# TESTESP1SH.net
KiCad netlist of a schematic drawn in EAGLE
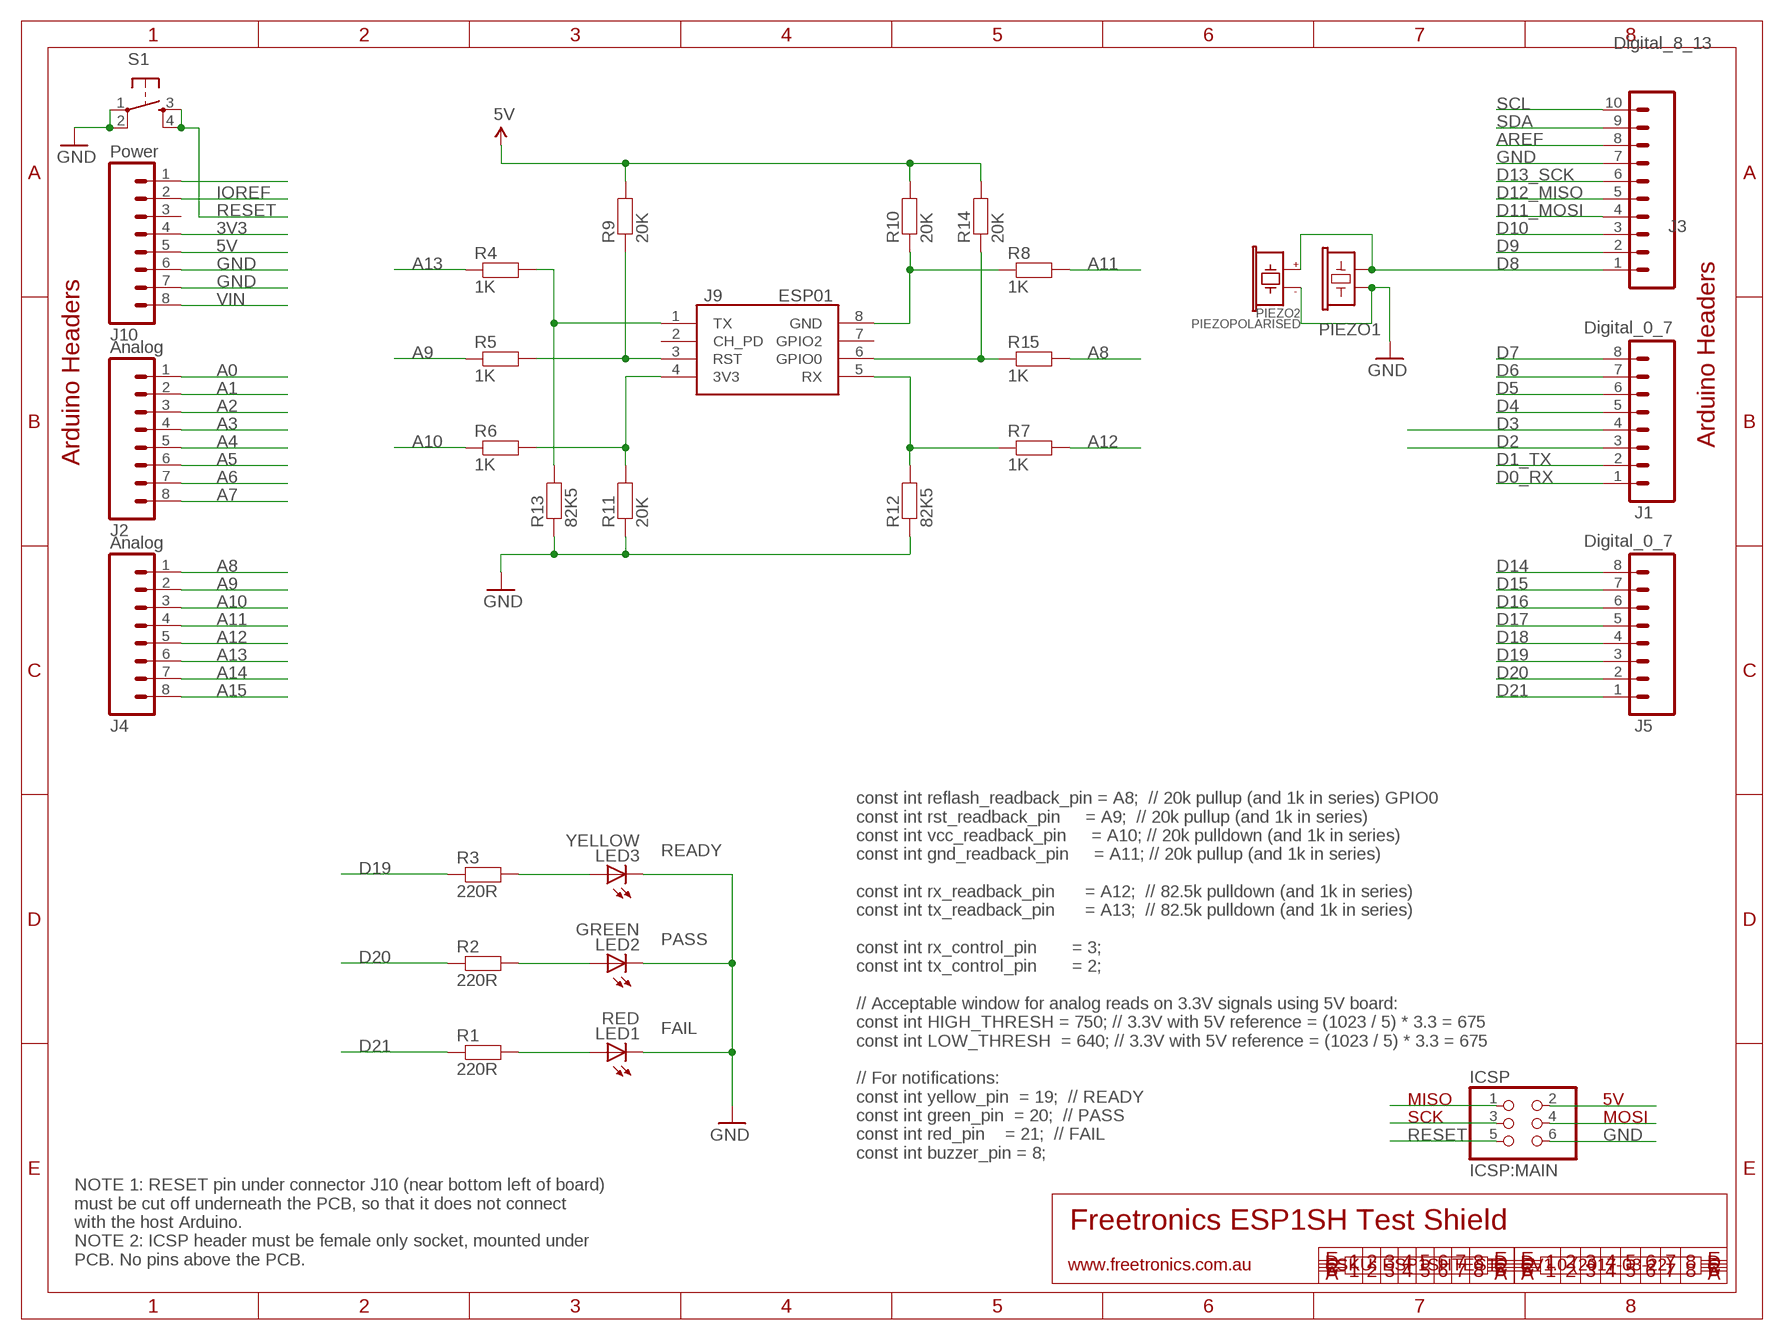
[diagram p0: schematic, sheet 1]

(export (version "E")
  (design (tool "Eeschema 10.0.6"))
  (components
    (comp (ref "ICSP")
      (value "ICSP:MAIN")
      (footprint "eagle-import:2X03")
      (libsource (lib "eagle-import") (part "PINHD-2X3"))
    )
    (comp (ref "J1")
      (value "Digital_0_7")
      (footprint "eagle-import:1X08")
      (libsource (lib "eagle-import") (part "M08"))
    )
    (comp (ref "J2")
      (value "Analog")
      (footprint "eagle-import:1X08")
      (libsource (lib "eagle-import") (part "freetronics-master-v1_M08"))
    )
    (comp (ref "J3")
      (value "Digital_8_13")
      (footprint "eagle-import:1X10")
      (libsource (lib "eagle-import") (part "M100.1"))
    )
    (comp (ref "J4")
      (value "Analog")
      (footprint "eagle-import:1X08")
      (libsource (lib "eagle-import") (part "freetronics-master-v1_M08"))
    )
    (comp (ref "J5")
      (value "Digital_0_7")
      (footprint "eagle-import:1X08")
      (libsource (lib "eagle-import") (part "M08"))
    )
    (comp (ref "J9")
      (value "ESP01")
      (footprint "eagle-import:ESP01")
      (libsource (lib "eagle-import") (part "ESP01"))
    )
    (comp (ref "J10")
      (value "Power")
      (footprint "eagle-import:1X08")
      (libsource (lib "eagle-import") (part "freetronics-master-v1_M08"))
    )
    (comp (ref "LED1")
      (value "RED")
      (footprint "eagle-import:LED-0603")
      (libsource (lib "eagle-import") (part "LED0603"))
    )
    (comp (ref "LED2")
      (value "GREEN")
      (footprint "eagle-import:LED-0603")
      (libsource (lib "eagle-import") (part "LED0603"))
    )
    (comp (ref "LED3")
      (value "YELLOW")
      (footprint "eagle-import:LED-0603")
      (libsource (lib "eagle-import") (part "LED0603"))
    )
    (comp (ref "PIEZO1")
      (value "BUZZERSMD12X12")
      (footprint "eagle-import:BUZZER-12X12-SMT")
      (libsource (lib "eagle-import") (part "BUZZERSMD12X12"))
    )
    (comp (ref "PIEZO2")
      (value "PIEZOPOLARISED")
      (footprint "eagle-import:PIEZO12MMWIDEPOLARISED")
      (libsource (lib "eagle-import") (part "PIEZOPOLARISED"))
    )
    (comp (ref "R1")
      (value "220R")
      (footprint "eagle-import:0603")
      (libsource (lib "eagle-import") (part "RESISTOR0603"))
    )
    (comp (ref "R2")
      (value "220R")
      (footprint "eagle-import:0603")
      (libsource (lib "eagle-import") (part "RESISTOR0603"))
    )
    (comp (ref "R3")
      (value "220R")
      (footprint "eagle-import:0603")
      (libsource (lib "eagle-import") (part "RESISTOR0603"))
    )
    (comp (ref "R4")
      (value "1K")
      (footprint "eagle-import:0603")
      (libsource (lib "eagle-import") (part "RESISTOR0603"))
    )
    (comp (ref "R5")
      (value "1K")
      (footprint "eagle-import:0603")
      (libsource (lib "eagle-import") (part "RESISTOR0603"))
    )
    (comp (ref "R6")
      (value "1K")
      (footprint "eagle-import:0603")
      (libsource (lib "eagle-import") (part "RESISTOR0603"))
    )
    (comp (ref "R7")
      (value "1K")
      (footprint "eagle-import:0603")
      (libsource (lib "eagle-import") (part "RESISTOR0603"))
    )
    (comp (ref "R8")
      (value "1K")
      (footprint "eagle-import:0603")
      (libsource (lib "eagle-import") (part "RESISTOR0603"))
    )
    (comp (ref "R9")
      (value "20K")
      (footprint "eagle-import:0603")
      (libsource (lib "eagle-import") (part "RESISTOR0603"))
    )
    (comp (ref "R10")
      (value "20K")
      (footprint "eagle-import:0603")
      (libsource (lib "eagle-import") (part "RESISTOR0603"))
    )
    (comp (ref "R11")
      (value "20K")
      (footprint "eagle-import:0603")
      (libsource (lib "eagle-import") (part "RESISTOR0603"))
    )
    (comp (ref "R12")
      (value "82K5")
      (footprint "eagle-import:0603")
      (libsource (lib "eagle-import") (part "RESISTOR0603"))
    )
    (comp (ref "R13")
      (value "82K5")
      (footprint "eagle-import:0603")
      (libsource (lib "eagle-import") (part "RESISTOR0603"))
    )
    (comp (ref "R14")
      (value "20K")
      (footprint "eagle-import:0603")
      (libsource (lib "eagle-import") (part "RESISTOR0603"))
    )
    (comp (ref "R15")
      (value "1K")
      (footprint "eagle-import:0603")
      (libsource (lib "eagle-import") (part "RESISTOR0603"))
    )
    (comp (ref "S1")
      (value "TAC_SWITCHPTH")
      (footprint "eagle-import:TACTILE-PTH")
      (libsource (lib "eagle-import") (part "TAC_SWITCHPTH"))
    )
  )
  (nets
    (net (code "1") (name "/3V3") (class "Default")
      (node (ref "J10") (pin "4") (pinfunction "4_4") (pintype "passive"))
    )
    (net (code "2") (name "/A0") (class "Default")
      (node (ref "J2") (pin "1") (pinfunction "1_1") (pintype "passive"))
    )
    (net (code "3") (name "/A1") (class "Default")
      (node (ref "J2") (pin "2") (pinfunction "2_2") (pintype "passive"))
    )
    (net (code "4") (name "/A2") (class "Default")
      (node (ref "J2") (pin "3") (pinfunction "3_3") (pintype "passive"))
    )
    (net (code "5") (name "/A3") (class "Default")
      (node (ref "J2") (pin "4") (pinfunction "4_4") (pintype "passive"))
    )
    (net (code "6") (name "/A4") (class "Default")
      (node (ref "J2") (pin "5") (pinfunction "5_5") (pintype "passive"))
    )
    (net (code "7") (name "/A5") (class "Default")
      (node (ref "J2") (pin "6") (pinfunction "6_6") (pintype "passive"))
    )
    (net (code "8") (name "/A6") (class "Default")
      (node (ref "J2") (pin "7") (pinfunction "7_7") (pintype "passive"))
    )
    (net (code "9") (name "/A7") (class "Default")
      (node (ref "J2") (pin "8") (pinfunction "8_8") (pintype "passive"))
    )
    (net (code "10") (name "/A8") (class "Default")
      (node (ref "J4") (pin "1") (pinfunction "1_1") (pintype "passive"))
      (node (ref "R15") (pin "2") (pinfunction "2_2") (pintype "passive"))
    )
    (net (code "11") (name "/A9") (class "Default")
      (node (ref "J4") (pin "2") (pinfunction "2_2") (pintype "passive"))
      (node (ref "R5") (pin "1") (pinfunction "1_1") (pintype "passive"))
    )
    (net (code "12") (name "/A10") (class "Default")
      (node (ref "J4") (pin "3") (pinfunction "3_3") (pintype "passive"))
      (node (ref "R6") (pin "1") (pinfunction "1_1") (pintype "passive"))
    )
    (net (code "13") (name "/A11") (class "Default")
      (node (ref "J4") (pin "4") (pinfunction "4_4") (pintype "passive"))
      (node (ref "R8") (pin "2") (pinfunction "2_2") (pintype "passive"))
    )
    (net (code "14") (name "/A12") (class "Default")
      (node (ref "J4") (pin "5") (pinfunction "5_5") (pintype "passive"))
      (node (ref "R7") (pin "2") (pinfunction "2_2") (pintype "passive"))
    )
    (net (code "15") (name "/A13") (class "Default")
      (node (ref "J4") (pin "6") (pinfunction "6_6") (pintype "passive"))
      (node (ref "R4") (pin "1") (pinfunction "1_1") (pintype "passive"))
    )
    (net (code "16") (name "/A14") (class "Default")
      (node (ref "J4") (pin "7") (pinfunction "7_7") (pintype "passive"))
    )
    (net (code "17") (name "/A15") (class "Default")
      (node (ref "J4") (pin "8") (pinfunction "8_8") (pintype "passive"))
    )
    (net (code "18") (name "/AREF") (class "Default")
      (node (ref "J3") (pin "8") (pinfunction "8_8") (pintype "passive"))
    )
    (net (code "19") (name "/D0_RX") (class "Default")
      (node (ref "J1") (pin "1") (pinfunction "1_1") (pintype "passive"))
    )
    (net (code "20") (name "/D1_TX") (class "Default")
      (node (ref "J1") (pin "2") (pinfunction "2_2") (pintype "passive"))
    )
    (net (code "21") (name "/D2") (class "Default")
      (node (ref "J1") (pin "3") (pinfunction "3_3") (pintype "passive"))
    )
    (net (code "22") (name "/D3") (class "Default")
      (node (ref "J1") (pin "4") (pinfunction "4_4") (pintype "passive"))
    )
    (net (code "23") (name "/D4") (class "Default")
      (node (ref "J1") (pin "5") (pinfunction "5_5") (pintype "passive"))
    )
    (net (code "24") (name "/D5") (class "Default")
      (node (ref "J1") (pin "6") (pinfunction "6_6") (pintype "passive"))
    )
    (net (code "25") (name "/D6") (class "Default")
      (node (ref "J1") (pin "7") (pinfunction "7_7") (pintype "passive"))
    )
    (net (code "26") (name "/D7") (class "Default")
      (node (ref "J1") (pin "8") (pinfunction "8_8") (pintype "passive"))
    )
    (net (code "27") (name "/D8") (class "Default")
      (node (ref "J3") (pin "1") (pinfunction "1_1") (pintype "passive"))
      (node (ref "PIEZO1") (pin "1") (pinfunction "1_1") (pintype "passive"))
      (node (ref "PIEZO2") (pin "1") (pinfunction "+_1") (pintype "bidirectional"))
    )
    (net (code "28") (name "/D9") (class "Default")
      (node (ref "J3") (pin "2") (pinfunction "2_2") (pintype "passive"))
    )
    (net (code "29") (name "/D10") (class "Default")
      (node (ref "J3") (pin "3") (pinfunction "3_3") (pintype "passive"))
    )
    (net (code "30") (name "/D11_MOSI") (class "Default")
      (node (ref "J3") (pin "4") (pinfunction "4_4") (pintype "passive"))
    )
    (net (code "31") (name "/D12_MISO") (class "Default")
      (node (ref "J3") (pin "5") (pinfunction "5_5") (pintype "passive"))
    )
    (net (code "32") (name "/D13_SCK") (class "Default")
      (node (ref "J3") (pin "6") (pinfunction "6_6") (pintype "passive"))
    )
    (net (code "33") (name "/D14") (class "Default")
      (node (ref "J5") (pin "8") (pinfunction "8_8") (pintype "passive"))
    )
    (net (code "34") (name "/D15") (class "Default")
      (node (ref "J5") (pin "7") (pinfunction "7_7") (pintype "passive"))
    )
    (net (code "35") (name "/D16") (class "Default")
      (node (ref "J5") (pin "6") (pinfunction "6_6") (pintype "passive"))
    )
    (net (code "36") (name "/D17") (class "Default")
      (node (ref "J5") (pin "5") (pinfunction "5_5") (pintype "passive"))
    )
    (net (code "37") (name "/D18") (class "Default")
      (node (ref "J5") (pin "4") (pinfunction "4_4") (pintype "passive"))
    )
    (net (code "38") (name "/D19") (class "Default")
      (node (ref "J5") (pin "3") (pinfunction "3_3") (pintype "passive"))
      (node (ref "R3") (pin "1") (pinfunction "1_1") (pintype "passive"))
    )
    (net (code "39") (name "/D20") (class "Default")
      (node (ref "J5") (pin "2") (pinfunction "2_2") (pintype "passive"))
      (node (ref "R2") (pin "1") (pinfunction "1_1") (pintype "passive"))
    )
    (net (code "40") (name "/D21") (class "Default")
      (node (ref "J5") (pin "1") (pinfunction "1_1") (pintype "passive"))
      (node (ref "R1") (pin "1") (pinfunction "1_1") (pintype "passive"))
    )
    (net (code "41") (name "/IOREF") (class "Default")
      (node (ref "J10") (pin "2") (pinfunction "2_2") (pintype "passive"))
    )
    (net (code "42") (name "/RESET") (class "Default")
      (node (ref "ICSP") (pin "5") (pinfunction "5_5") (pintype "passive"))
      (node (ref "S1") (pin "3") (pinfunction "3_3") (pintype "passive"))
      (node (ref "S1") (pin "4") (pinfunction "4_4") (pintype "passive"))
    )
    (net (code "43") (name "/SCL") (class "Default")
      (node (ref "J3") (pin "10") (pinfunction "10_10") (pintype "passive"))
    )
    (net (code "44") (name "/SDA") (class "Default")
      (node (ref "J3") (pin "9") (pinfunction "9_9") (pintype "passive"))
    )
    (net (code "45") (name "/VIN") (class "Default")
      (node (ref "J10") (pin "8") (pinfunction "8_8") (pintype "passive"))
    )
    (net (code "46") (name "5V") (class "Default")
      (node (ref "J10") (pin "5") (pinfunction "5_5") (pintype "passive"))
      (node (ref "R10") (pin "2") (pinfunction "2_2") (pintype "passive"))
      (node (ref "R14") (pin "2") (pinfunction "2_2") (pintype "passive"))
      (node (ref "R9") (pin "2") (pinfunction "2_2") (pintype "passive"))
    )
    (net (code "47") (name "GND") (class "Default")
      (node (ref "ICSP") (pin "6") (pinfunction "6_6") (pintype "passive"))
      (node (ref "J10") (pin "6") (pinfunction "6_6") (pintype "passive"))
      (node (ref "J10") (pin "7") (pinfunction "7_7") (pintype "passive"))
      (node (ref "J3") (pin "7") (pinfunction "7_7") (pintype "passive"))
      (node (ref "LED1") (pin "C") (pinfunction "C_C") (pintype "passive"))
      (node (ref "LED2") (pin "C") (pinfunction "C_C") (pintype "passive"))
      (node (ref "LED3") (pin "C") (pinfunction "C_C") (pintype "passive"))
      (node (ref "PIEZO1") (pin "2") (pinfunction "2_2") (pintype "passive"))
      (node (ref "PIEZO2") (pin "2") (pinfunction "-_2") (pintype "bidirectional"))
      (node (ref "R11") (pin "1") (pinfunction "1_1") (pintype "passive"))
      (node (ref "R12") (pin "1") (pinfunction "1_1") (pintype "passive"))
      (node (ref "R13") (pin "1") (pinfunction "1_1") (pintype "passive"))
      (node (ref "S1") (pin "1") (pinfunction "1_1") (pintype "passive"))
      (node (ref "S1") (pin "2") (pinfunction "2_2") (pintype "passive"))
    )
    (net (code "48") (name "Net-(J9-3V3)") (class "Default")
      (node (ref "J9") (pin "4") (pinfunction "3V3_4") (pintype "bidirectional"))
      (node (ref "R11") (pin "2") (pinfunction "2_2") (pintype "passive"))
      (node (ref "R6") (pin "2") (pinfunction "2_2") (pintype "passive"))
    )
    (net (code "49") (name "Net-(J9-GND)") (class "Default")
      (node (ref "J9") (pin "8") (pinfunction "GND_8") (pintype "bidirectional"))
      (node (ref "R10") (pin "1") (pinfunction "1_1") (pintype "passive"))
      (node (ref "R8") (pin "1") (pinfunction "1_1") (pintype "passive"))
    )
    (net (code "50") (name "Net-(J9-GPIO0)") (class "Default")
      (node (ref "J9") (pin "6") (pinfunction "GPIO0_6") (pintype "bidirectional"))
      (node (ref "R14") (pin "1") (pinfunction "1_1") (pintype "passive"))
      (node (ref "R15") (pin "1") (pinfunction "1_1") (pintype "passive"))
    )
    (net (code "51") (name "Net-(J9-RST)") (class "Default")
      (node (ref "J9") (pin "3") (pinfunction "RST_3") (pintype "bidirectional"))
      (node (ref "R5") (pin "2") (pinfunction "2_2") (pintype "passive"))
      (node (ref "R9") (pin "1") (pinfunction "1_1") (pintype "passive"))
    )
    (net (code "52") (name "Net-(J9-RX)") (class "Default")
      (node (ref "J9") (pin "5") (pinfunction "RX_5") (pintype "bidirectional"))
      (node (ref "R12") (pin "2") (pinfunction "2_2") (pintype "passive"))
      (node (ref "R7") (pin "1") (pinfunction "1_1") (pintype "passive"))
    )
    (net (code "53") (name "Net-(J9-TX)") (class "Default")
      (node (ref "J9") (pin "1") (pinfunction "TX_1") (pintype "bidirectional"))
      (node (ref "R13") (pin "2") (pinfunction "2_2") (pintype "passive"))
      (node (ref "R4") (pin "2") (pinfunction "2_2") (pintype "passive"))
    )
    (net (code "54") (name "Net-(LED1-PadA)") (class "Default")
      (node (ref "LED1") (pin "A") (pinfunction "A_A") (pintype "passive"))
      (node (ref "R1") (pin "2") (pinfunction "2_2") (pintype "passive"))
    )
    (net (code "55") (name "Net-(LED2-PadA)") (class "Default")
      (node (ref "LED2") (pin "A") (pinfunction "A_A") (pintype "passive"))
      (node (ref "R2") (pin "2") (pinfunction "2_2") (pintype "passive"))
    )
    (net (code "56") (name "Net-(LED3-PadA)") (class "Default")
      (node (ref "LED3") (pin "A") (pinfunction "A_A") (pintype "passive"))
      (node (ref "R3") (pin "2") (pinfunction "2_2") (pintype "passive"))
    )
    (net (code "57") (name "unconnected-(ICSP-Pad1)") (class "Default")
      (node (ref "ICSP") (pin "1") (pinfunction "1_1") (pintype "passive"))
    )
    (net (code "58") (name "unconnected-(ICSP-Pad2)") (class "Default")
      (node (ref "ICSP") (pin "2") (pinfunction "2_2") (pintype "passive"))
    )
    (net (code "59") (name "unconnected-(ICSP-Pad3)") (class "Default")
      (node (ref "ICSP") (pin "3") (pinfunction "3_3") (pintype "passive"))
    )
    (net (code "60") (name "unconnected-(ICSP-Pad4)") (class "Default")
      (node (ref "ICSP") (pin "4") (pinfunction "4_4") (pintype "passive"))
    )
    (net (code "61") (name "unconnected-(J9-CH_PD-Pad2)") (class "Default")
      (node (ref "J9") (pin "2") (pinfunction "CH_PD_2") (pintype "bidirectional"))
    )
    (net (code "62") (name "unconnected-(J9-GPIO2-Pad7)") (class "Default")
      (node (ref "J9") (pin "7") (pinfunction "GPIO2_7") (pintype "bidirectional"))
    )
    (net (code "63") (name "unconnected-(J10-Pad1)") (class "Default")
      (node (ref "J10") (pin "1") (pinfunction "1_1") (pintype "passive"))
    )
    (net (code "64") (name "unconnected-(J10-Pad3)") (class "Default")
      (node (ref "J10") (pin "3") (pinfunction "3_3") (pintype "passive"))
    )
  )
)
